# IO_Expander.net
KiCad netlist of a schematic drawn in EAGLE
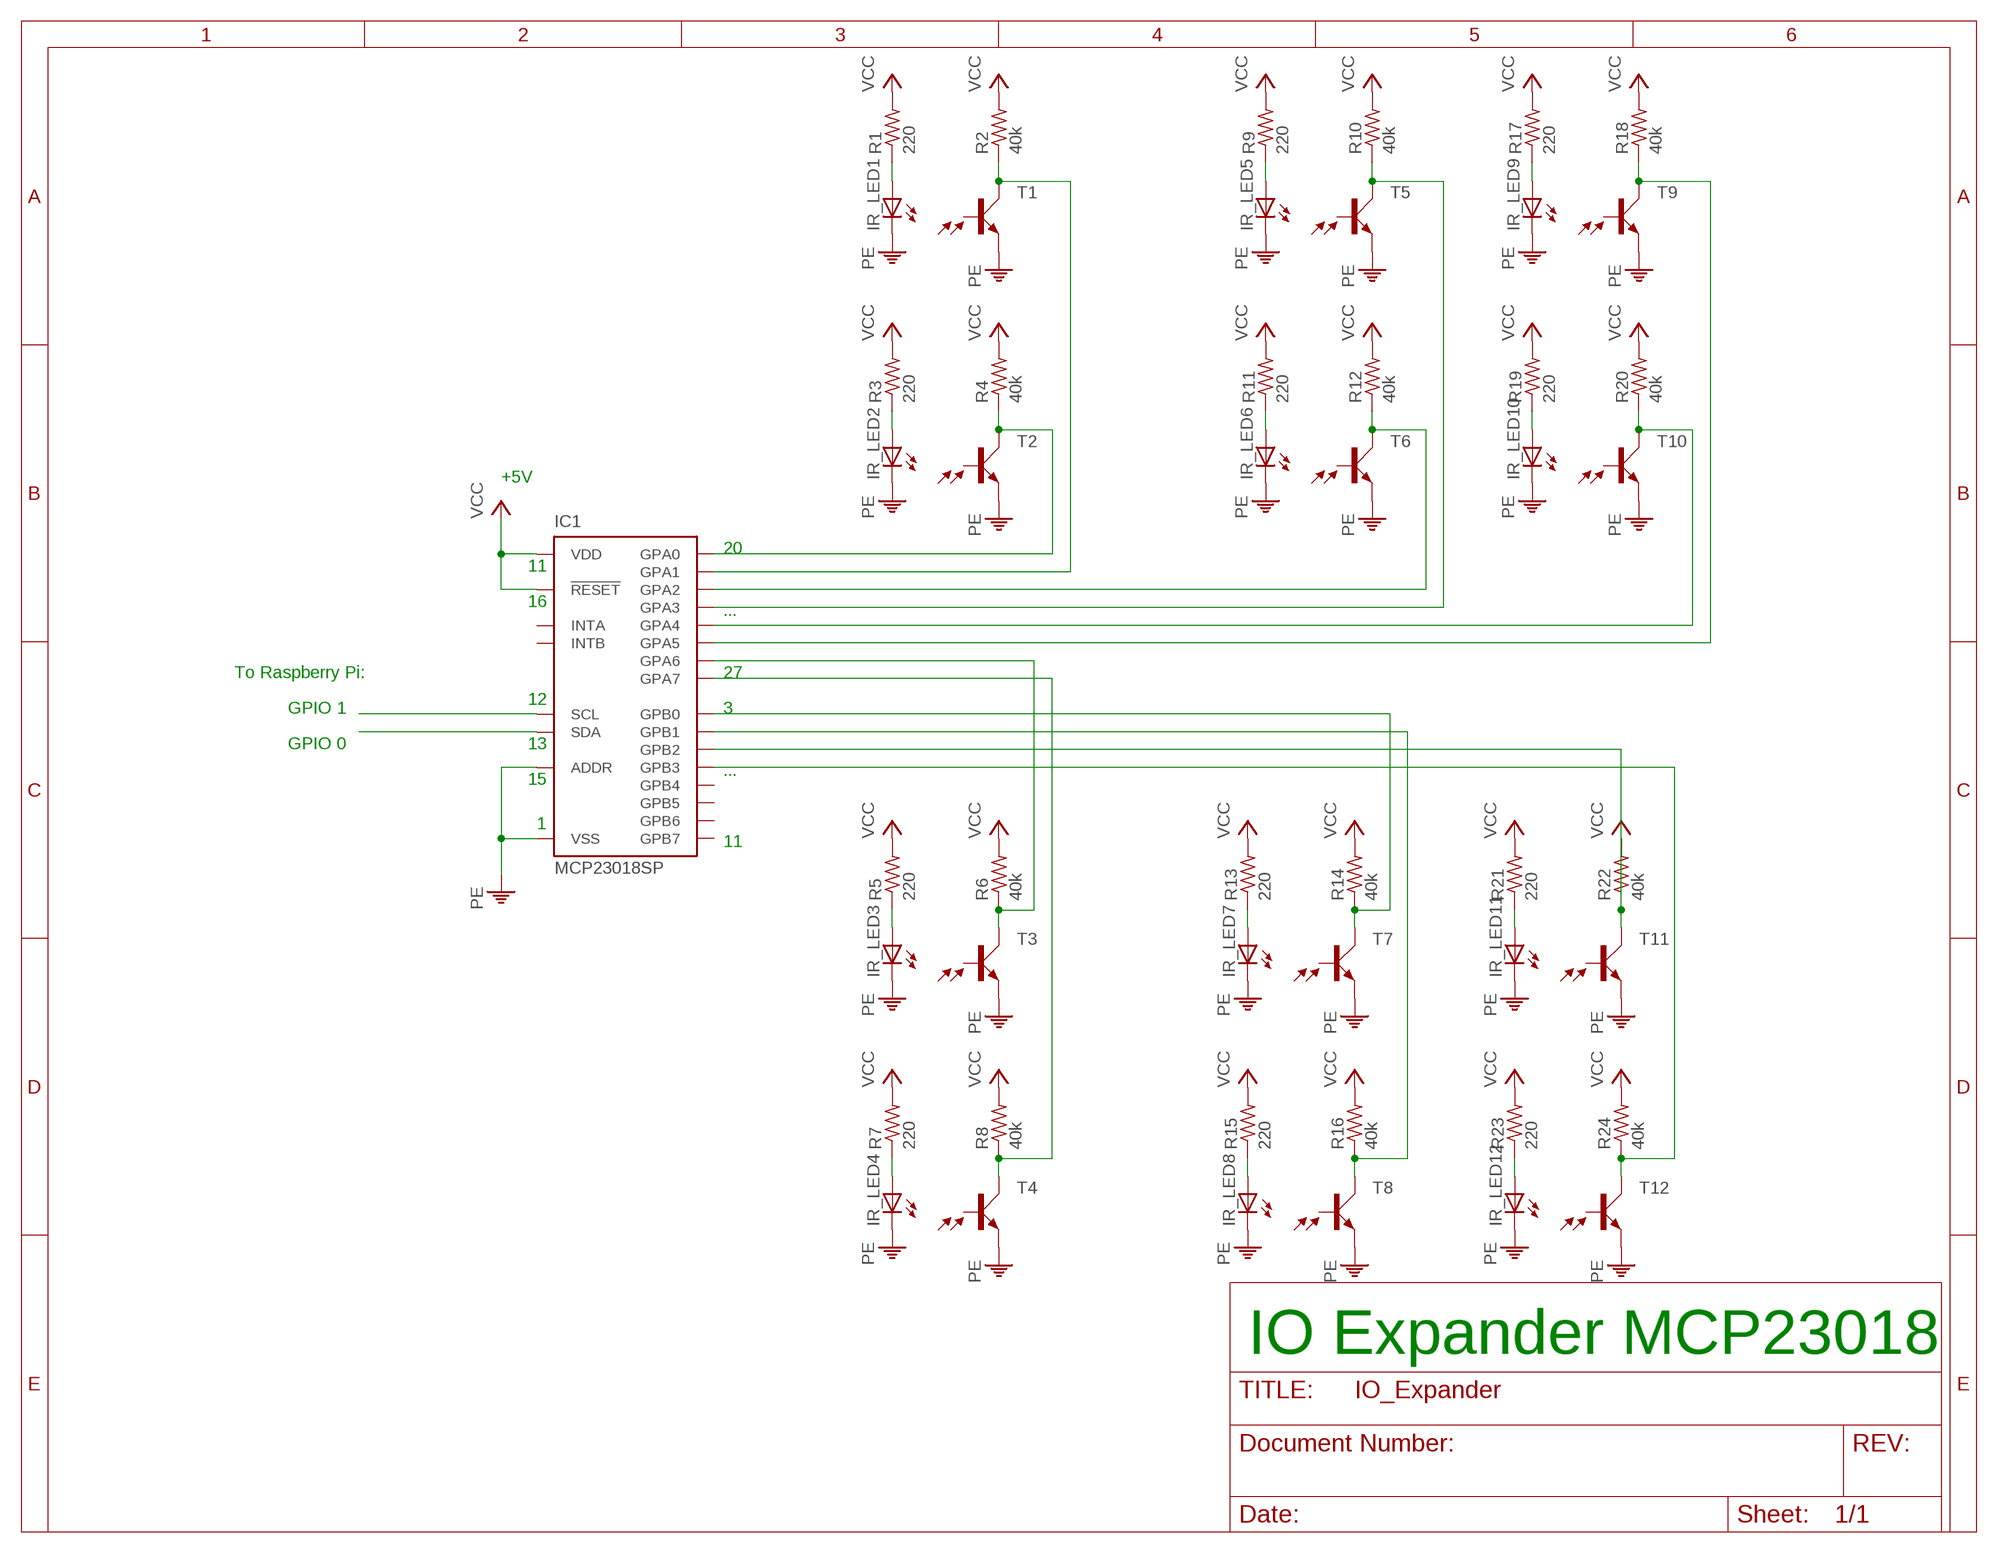
[diagram p0: schematic, sheet 1]

(export (version "E")
  (design (tool "Eeschema 10.0.6"))
  (components
    (comp (ref "IC1")
      (value "MCP23018SP")
      (footprint "eagle-import:DIL28-3")
      (libsource (lib "eagle-import") (part "MCP23018SP"))
    )
    (comp (ref "IR_LED1")
      (value "LED5MM")
      (footprint "eagle-import:LED5MM")
      (libsource (lib "eagle-import") (part "LED5MM"))
    )
    (comp (ref "IR_LED2")
      (value "LED5MM")
      (footprint "eagle-import:LED5MM")
      (libsource (lib "eagle-import") (part "LED5MM"))
    )
    (comp (ref "IR_LED3")
      (value "LED5MM")
      (footprint "eagle-import:LED5MM")
      (libsource (lib "eagle-import") (part "LED5MM"))
    )
    (comp (ref "IR_LED4")
      (value "LED5MM")
      (footprint "eagle-import:LED5MM")
      (libsource (lib "eagle-import") (part "LED5MM"))
    )
    (comp (ref "IR_LED5")
      (value "LED5MM")
      (footprint "eagle-import:LED5MM")
      (libsource (lib "eagle-import") (part "LED5MM"))
    )
    (comp (ref "IR_LED6")
      (value "LED5MM")
      (footprint "eagle-import:LED5MM")
      (libsource (lib "eagle-import") (part "LED5MM"))
    )
    (comp (ref "IR_LED7")
      (value "LED5MM")
      (footprint "eagle-import:LED5MM")
      (libsource (lib "eagle-import") (part "LED5MM"))
    )
    (comp (ref "IR_LED8")
      (value "LED5MM")
      (footprint "eagle-import:LED5MM")
      (libsource (lib "eagle-import") (part "LED5MM"))
    )
    (comp (ref "IR_LED9")
      (value "LED5MM")
      (footprint "eagle-import:LED5MM")
      (libsource (lib "eagle-import") (part "LED5MM"))
    )
    (comp (ref "IR_LED10")
      (value "LED5MM")
      (footprint "eagle-import:LED5MM")
      (libsource (lib "eagle-import") (part "LED5MM"))
    )
    (comp (ref "IR_LED11")
      (value "LED5MM")
      (footprint "eagle-import:LED5MM")
      (libsource (lib "eagle-import") (part "LED5MM"))
    )
    (comp (ref "IR_LED12")
      (value "LED5MM")
      (footprint "eagle-import:LED5MM")
      (libsource (lib "eagle-import") (part "LED5MM"))
    )
    (comp (ref "R1")
      (value "220")
      (footprint "eagle-import:0204_7")
      (libsource (lib "eagle-import") (part "R-US_0204/7"))
    )
    (comp (ref "R2")
      (value "40k")
      (footprint "eagle-import:0204_7")
      (libsource (lib "eagle-import") (part "R-US_0204/7"))
    )
    (comp (ref "R3")
      (value "220")
      (footprint "eagle-import:0204_7")
      (libsource (lib "eagle-import") (part "R-US_0204/7"))
    )
    (comp (ref "R4")
      (value "40k")
      (footprint "eagle-import:0204_7")
      (libsource (lib "eagle-import") (part "R-US_0204/7"))
    )
    (comp (ref "R5")
      (value "220")
      (footprint "eagle-import:0204_7")
      (libsource (lib "eagle-import") (part "R-US_0204/7"))
    )
    (comp (ref "R6")
      (value "40k")
      (footprint "eagle-import:0204_7")
      (libsource (lib "eagle-import") (part "R-US_0204/7"))
    )
    (comp (ref "R7")
      (value "220")
      (footprint "eagle-import:0204_7")
      (libsource (lib "eagle-import") (part "R-US_0204/7"))
    )
    (comp (ref "R8")
      (value "40k")
      (footprint "eagle-import:0204_7")
      (libsource (lib "eagle-import") (part "R-US_0204/7"))
    )
    (comp (ref "R9")
      (value "220")
      (footprint "eagle-import:0204_7")
      (libsource (lib "eagle-import") (part "R-US_0204/7"))
    )
    (comp (ref "R10")
      (value "40k")
      (footprint "eagle-import:0204_7")
      (libsource (lib "eagle-import") (part "R-US_0204/7"))
    )
    (comp (ref "R11")
      (value "220")
      (footprint "eagle-import:0204_7")
      (libsource (lib "eagle-import") (part "R-US_0204/7"))
    )
    (comp (ref "R12")
      (value "40k")
      (footprint "eagle-import:0204_7")
      (libsource (lib "eagle-import") (part "R-US_0204/7"))
    )
    (comp (ref "R13")
      (value "220")
      (footprint "eagle-import:0204_7")
      (libsource (lib "eagle-import") (part "R-US_0204/7"))
    )
    (comp (ref "R14")
      (value "40k")
      (footprint "eagle-import:0204_7")
      (libsource (lib "eagle-import") (part "R-US_0204/7"))
    )
    (comp (ref "R15")
      (value "220")
      (footprint "eagle-import:0204_7")
      (libsource (lib "eagle-import") (part "R-US_0204/7"))
    )
    (comp (ref "R16")
      (value "40k")
      (footprint "eagle-import:0204_7")
      (libsource (lib "eagle-import") (part "R-US_0204/7"))
    )
    (comp (ref "R17")
      (value "220")
      (footprint "eagle-import:0204_7")
      (libsource (lib "eagle-import") (part "R-US_0204/7"))
    )
    (comp (ref "R18")
      (value "40k")
      (footprint "eagle-import:0204_7")
      (libsource (lib "eagle-import") (part "R-US_0204/7"))
    )
    (comp (ref "R19")
      (value "220")
      (footprint "eagle-import:0204_7")
      (libsource (lib "eagle-import") (part "R-US_0204/7"))
    )
    (comp (ref "R20")
      (value "40k")
      (footprint "eagle-import:0204_7")
      (libsource (lib "eagle-import") (part "R-US_0204/7"))
    )
    (comp (ref "R21")
      (value "220")
      (footprint "eagle-import:0204_7")
      (libsource (lib "eagle-import") (part "R-US_0204/7"))
    )
    (comp (ref "R22")
      (value "40k")
      (footprint "eagle-import:0204_7")
      (libsource (lib "eagle-import") (part "R-US_0204/7"))
    )
    (comp (ref "R23")
      (value "220")
      (footprint "eagle-import:0204_7")
      (libsource (lib "eagle-import") (part "R-US_0204/7"))
    )
    (comp (ref "R24")
      (value "40k")
      (footprint "eagle-import:0204_7")
      (libsource (lib "eagle-import") (part "R-US_0204/7"))
    )
    (comp (ref "T1")
      (value "SFH303")
      (footprint "eagle-import:SFH303")
      (libsource (lib "eagle-import") (part "SFH303"))
    )
    (comp (ref "T2")
      (value "SFH303")
      (footprint "eagle-import:SFH303")
      (libsource (lib "eagle-import") (part "SFH303"))
    )
    (comp (ref "T3")
      (value "SFH303")
      (footprint "eagle-import:SFH303")
      (libsource (lib "eagle-import") (part "SFH303"))
    )
    (comp (ref "T4")
      (value "SFH303")
      (footprint "eagle-import:SFH303")
      (libsource (lib "eagle-import") (part "SFH303"))
    )
    (comp (ref "T5")
      (value "SFH303")
      (footprint "eagle-import:SFH303")
      (libsource (lib "eagle-import") (part "SFH303"))
    )
    (comp (ref "T6")
      (value "SFH303")
      (footprint "eagle-import:SFH303")
      (libsource (lib "eagle-import") (part "SFH303"))
    )
    (comp (ref "T7")
      (value "SFH303")
      (footprint "eagle-import:SFH303")
      (libsource (lib "eagle-import") (part "SFH303"))
    )
    (comp (ref "T8")
      (value "SFH303")
      (footprint "eagle-import:SFH303")
      (libsource (lib "eagle-import") (part "SFH303"))
    )
    (comp (ref "T9")
      (value "SFH303")
      (footprint "eagle-import:SFH303")
      (libsource (lib "eagle-import") (part "SFH303"))
    )
    (comp (ref "T10")
      (value "SFH303")
      (footprint "eagle-import:SFH303")
      (libsource (lib "eagle-import") (part "SFH303"))
    )
    (comp (ref "T11")
      (value "SFH303")
      (footprint "eagle-import:SFH303")
      (libsource (lib "eagle-import") (part "SFH303"))
    )
    (comp (ref "T12")
      (value "SFH303")
      (footprint "eagle-import:SFH303")
      (libsource (lib "eagle-import") (part "SFH303"))
    )
  )
  (nets
    (net (code "1") (name "Net-(IC1-GPA0)") (class "Default")
      (node (ref "IC1") (pin "20") (pinfunction "GPA0_20") (pintype "bidirectional"))
      (node (ref "R4") (pin "1") (pinfunction "1_1") (pintype "passive"))
      (node (ref "T2") (pin "2") (pinfunction "C_2") (pintype "passive"))
    )
    (net (code "2") (name "Net-(IC1-GPA1)") (class "Default")
      (node (ref "IC1") (pin "21") (pinfunction "GPA1_21") (pintype "bidirectional"))
      (node (ref "R2") (pin "1") (pinfunction "1_1") (pintype "passive"))
      (node (ref "T1") (pin "2") (pinfunction "C_2") (pintype "passive"))
    )
    (net (code "3") (name "Net-(IC1-GPA2)") (class "Default")
      (node (ref "IC1") (pin "22") (pinfunction "GPA2_22") (pintype "bidirectional"))
      (node (ref "R12") (pin "1") (pinfunction "1_1") (pintype "passive"))
      (node (ref "T6") (pin "2") (pinfunction "C_2") (pintype "passive"))
    )
    (net (code "4") (name "Net-(IC1-GPA3)") (class "Default")
      (node (ref "IC1") (pin "23") (pinfunction "GPA3_23") (pintype "bidirectional"))
      (node (ref "R10") (pin "1") (pinfunction "1_1") (pintype "passive"))
      (node (ref "T5") (pin "2") (pinfunction "C_2") (pintype "passive"))
    )
    (net (code "5") (name "Net-(IC1-GPA4)") (class "Default")
      (node (ref "IC1") (pin "24") (pinfunction "GPA4_24") (pintype "bidirectional"))
      (node (ref "R20") (pin "1") (pinfunction "1_1") (pintype "passive"))
      (node (ref "T10") (pin "2") (pinfunction "C_2") (pintype "passive"))
    )
    (net (code "6") (name "Net-(IC1-GPA5)") (class "Default")
      (node (ref "IC1") (pin "25") (pinfunction "GPA5_25") (pintype "bidirectional"))
      (node (ref "R18") (pin "1") (pinfunction "1_1") (pintype "passive"))
      (node (ref "T9") (pin "2") (pinfunction "C_2") (pintype "passive"))
    )
    (net (code "7") (name "Net-(IC1-GPA6)") (class "Default")
      (node (ref "IC1") (pin "26") (pinfunction "GPA6_26") (pintype "bidirectional"))
      (node (ref "R6") (pin "1") (pinfunction "1_1") (pintype "passive"))
      (node (ref "T3") (pin "2") (pinfunction "C_2") (pintype "passive"))
    )
    (net (code "8") (name "Net-(IC1-GPA7)") (class "Default")
      (node (ref "IC1") (pin "27") (pinfunction "GPA7_27") (pintype "bidirectional"))
      (node (ref "R8") (pin "1") (pinfunction "1_1") (pintype "passive"))
      (node (ref "T4") (pin "2") (pinfunction "C_2") (pintype "passive"))
    )
    (net (code "9") (name "Net-(IC1-GPB0)") (class "Default")
      (node (ref "IC1") (pin "3") (pinfunction "GPB0_3") (pintype "bidirectional"))
      (node (ref "R14") (pin "1") (pinfunction "1_1") (pintype "passive"))
      (node (ref "T7") (pin "2") (pinfunction "C_2") (pintype "passive"))
    )
    (net (code "10") (name "Net-(IC1-GPB1)") (class "Default")
      (node (ref "IC1") (pin "4") (pinfunction "GPB1_4") (pintype "bidirectional"))
      (node (ref "R16") (pin "1") (pinfunction "1_1") (pintype "passive"))
      (node (ref "T8") (pin "2") (pinfunction "C_2") (pintype "passive"))
    )
    (net (code "11") (name "Net-(IC1-GPB2)") (class "Default")
      (node (ref "IC1") (pin "5") (pinfunction "GPB2_5") (pintype "bidirectional"))
      (node (ref "R22") (pin "1") (pinfunction "1_1") (pintype "passive"))
      (node (ref "T11") (pin "2") (pinfunction "C_2") (pintype "passive"))
    )
    (net (code "12") (name "Net-(IC1-GPB3)") (class "Default")
      (node (ref "IC1") (pin "6") (pinfunction "GPB3_6") (pintype "bidirectional"))
      (node (ref "R24") (pin "1") (pinfunction "1_1") (pintype "passive"))
      (node (ref "T12") (pin "2") (pinfunction "C_2") (pintype "passive"))
    )
    (net (code "13") (name "Net-(IR_LED1-PadA)") (class "Default")
      (node (ref "IR_LED1") (pin "A") (pinfunction "A_A") (pintype "passive"))
      (node (ref "R1") (pin "1") (pinfunction "1_1") (pintype "passive"))
    )
    (net (code "14") (name "Net-(IR_LED2-PadA)") (class "Default")
      (node (ref "IR_LED2") (pin "A") (pinfunction "A_A") (pintype "passive"))
      (node (ref "R3") (pin "1") (pinfunction "1_1") (pintype "passive"))
    )
    (net (code "15") (name "Net-(IR_LED3-PadA)") (class "Default")
      (node (ref "IR_LED3") (pin "A") (pinfunction "A_A") (pintype "passive"))
      (node (ref "R5") (pin "1") (pinfunction "1_1") (pintype "passive"))
    )
    (net (code "16") (name "Net-(IR_LED4-PadA)") (class "Default")
      (node (ref "IR_LED4") (pin "A") (pinfunction "A_A") (pintype "passive"))
      (node (ref "R7") (pin "1") (pinfunction "1_1") (pintype "passive"))
    )
    (net (code "17") (name "Net-(IR_LED5-PadA)") (class "Default")
      (node (ref "IR_LED5") (pin "A") (pinfunction "A_A") (pintype "passive"))
      (node (ref "R9") (pin "1") (pinfunction "1_1") (pintype "passive"))
    )
    (net (code "18") (name "Net-(IR_LED6-PadA)") (class "Default")
      (node (ref "IR_LED6") (pin "A") (pinfunction "A_A") (pintype "passive"))
      (node (ref "R11") (pin "1") (pinfunction "1_1") (pintype "passive"))
    )
    (net (code "19") (name "Net-(IR_LED7-PadA)") (class "Default")
      (node (ref "IR_LED7") (pin "A") (pinfunction "A_A") (pintype "passive"))
      (node (ref "R13") (pin "1") (pinfunction "1_1") (pintype "passive"))
    )
    (net (code "20") (name "Net-(IR_LED8-PadA)") (class "Default")
      (node (ref "IR_LED8") (pin "A") (pinfunction "A_A") (pintype "passive"))
      (node (ref "R15") (pin "1") (pinfunction "1_1") (pintype "passive"))
    )
    (net (code "21") (name "Net-(IR_LED9-PadA)") (class "Default")
      (node (ref "IR_LED9") (pin "A") (pinfunction "A_A") (pintype "passive"))
      (node (ref "R17") (pin "1") (pinfunction "1_1") (pintype "passive"))
    )
    (net (code "22") (name "Net-(IR_LED10-PadA)") (class "Default")
      (node (ref "IR_LED10") (pin "A") (pinfunction "A_A") (pintype "passive"))
      (node (ref "R19") (pin "1") (pinfunction "1_1") (pintype "passive"))
    )
    (net (code "23") (name "Net-(IR_LED11-PadA)") (class "Default")
      (node (ref "IR_LED11") (pin "A") (pinfunction "A_A") (pintype "passive"))
      (node (ref "R21") (pin "1") (pinfunction "1_1") (pintype "passive"))
    )
    (net (code "24") (name "Net-(IR_LED12-PadA)") (class "Default")
      (node (ref "IR_LED12") (pin "A") (pinfunction "A_A") (pintype "passive"))
      (node (ref "R23") (pin "1") (pinfunction "1_1") (pintype "passive"))
    )
    (net (code "25") (name "PE") (class "Default")
      (node (ref "IC1") (pin "1") (pinfunction "VSS_1") (pintype "power_in"))
      (node (ref "IC1") (pin "15") (pinfunction "ADDR_15") (pintype "input"))
      (node (ref "IR_LED1") (pin "K") (pinfunction "C_K") (pintype "passive"))
      (node (ref "IR_LED10") (pin "K") (pinfunction "C_K") (pintype "passive"))
      (node (ref "IR_LED11") (pin "K") (pinfunction "C_K") (pintype "passive"))
      (node (ref "IR_LED12") (pin "K") (pinfunction "C_K") (pintype "passive"))
      (node (ref "IR_LED2") (pin "K") (pinfunction "C_K") (pintype "passive"))
      (node (ref "IR_LED3") (pin "K") (pinfunction "C_K") (pintype "passive"))
      (node (ref "IR_LED4") (pin "K") (pinfunction "C_K") (pintype "passive"))
      (node (ref "IR_LED5") (pin "K") (pinfunction "C_K") (pintype "passive"))
      (node (ref "IR_LED6") (pin "K") (pinfunction "C_K") (pintype "passive"))
      (node (ref "IR_LED7") (pin "K") (pinfunction "C_K") (pintype "passive"))
      (node (ref "IR_LED8") (pin "K") (pinfunction "C_K") (pintype "passive"))
      (node (ref "IR_LED9") (pin "K") (pinfunction "C_K") (pintype "passive"))
      (node (ref "T1") (pin "1") (pinfunction "E_1") (pintype "passive"))
      (node (ref "T10") (pin "1") (pinfunction "E_1") (pintype "passive"))
      (node (ref "T11") (pin "1") (pinfunction "E_1") (pintype "passive"))
      (node (ref "T12") (pin "1") (pinfunction "E_1") (pintype "passive"))
      (node (ref "T2") (pin "1") (pinfunction "E_1") (pintype "passive"))
      (node (ref "T3") (pin "1") (pinfunction "E_1") (pintype "passive"))
      (node (ref "T4") (pin "1") (pinfunction "E_1") (pintype "passive"))
      (node (ref "T5") (pin "1") (pinfunction "E_1") (pintype "passive"))
      (node (ref "T6") (pin "1") (pinfunction "E_1") (pintype "passive"))
      (node (ref "T7") (pin "1") (pinfunction "E_1") (pintype "passive"))
      (node (ref "T8") (pin "1") (pinfunction "E_1") (pintype "passive"))
      (node (ref "T9") (pin "1") (pinfunction "E_1") (pintype "passive"))
    )
    (net (code "26") (name "VCC") (class "Default")
      (node (ref "IC1") (pin "11") (pinfunction "VDD_11") (pintype "power_in"))
      (node (ref "IC1") (pin "16") (pinfunction "~{RESET}_16") (pintype "input"))
      (node (ref "R1") (pin "2") (pinfunction "2_2") (pintype "passive"))
      (node (ref "R10") (pin "2") (pinfunction "2_2") (pintype "passive"))
      (node (ref "R11") (pin "2") (pinfunction "2_2") (pintype "passive"))
      (node (ref "R12") (pin "2") (pinfunction "2_2") (pintype "passive"))
      (node (ref "R13") (pin "2") (pinfunction "2_2") (pintype "passive"))
      (node (ref "R14") (pin "2") (pinfunction "2_2") (pintype "passive"))
      (node (ref "R15") (pin "2") (pinfunction "2_2") (pintype "passive"))
      (node (ref "R16") (pin "2") (pinfunction "2_2") (pintype "passive"))
      (node (ref "R17") (pin "2") (pinfunction "2_2") (pintype "passive"))
      (node (ref "R18") (pin "2") (pinfunction "2_2") (pintype "passive"))
      (node (ref "R19") (pin "2") (pinfunction "2_2") (pintype "passive"))
      (node (ref "R2") (pin "2") (pinfunction "2_2") (pintype "passive"))
      (node (ref "R20") (pin "2") (pinfunction "2_2") (pintype "passive"))
      (node (ref "R21") (pin "2") (pinfunction "2_2") (pintype "passive"))
      (node (ref "R22") (pin "2") (pinfunction "2_2") (pintype "passive"))
      (node (ref "R23") (pin "2") (pinfunction "2_2") (pintype "passive"))
      (node (ref "R24") (pin "2") (pinfunction "2_2") (pintype "passive"))
      (node (ref "R3") (pin "2") (pinfunction "2_2") (pintype "passive"))
      (node (ref "R4") (pin "2") (pinfunction "2_2") (pintype "passive"))
      (node (ref "R5") (pin "2") (pinfunction "2_2") (pintype "passive"))
      (node (ref "R6") (pin "2") (pinfunction "2_2") (pintype "passive"))
      (node (ref "R7") (pin "2") (pinfunction "2_2") (pintype "passive"))
      (node (ref "R8") (pin "2") (pinfunction "2_2") (pintype "passive"))
      (node (ref "R9") (pin "2") (pinfunction "2_2") (pintype "passive"))
    )
    (net (code "27") (name "unconnected-(IC1-GPB4-Pad7)") (class "Default")
      (node (ref "IC1") (pin "7") (pinfunction "GPB4_7") (pintype "bidirectional"))
    )
    (net (code "28") (name "unconnected-(IC1-GPB5-Pad8)") (class "Default")
      (node (ref "IC1") (pin "8") (pinfunction "GPB5_8") (pintype "bidirectional"))
    )
    (net (code "29") (name "unconnected-(IC1-GPB6-Pad9)") (class "Default")
      (node (ref "IC1") (pin "9") (pinfunction "GPB6_9") (pintype "bidirectional"))
    )
    (net (code "30") (name "unconnected-(IC1-GPB7-Pad10)") (class "Default")
      (node (ref "IC1") (pin "10") (pinfunction "GPB7_10") (pintype "bidirectional"))
    )
    (net (code "31") (name "unconnected-(IC1-INTA-Pad19)") (class "Default")
      (node (ref "IC1") (pin "19") (pinfunction "INTA_19") (pintype "output"))
    )
    (net (code "32") (name "unconnected-(IC1-INTB-Pad18)") (class "Default")
      (node (ref "IC1") (pin "18") (pinfunction "INTB_18") (pintype "output"))
    )
    (net (code "33") (name "unconnected-(IC1-SCL-Pad12)") (class "Default")
      (node (ref "IC1") (pin "12") (pinfunction "SCL_12") (pintype "input"))
    )
    (net (code "34") (name "unconnected-(IC1-SDA-Pad13)") (class "Default")
      (node (ref "IC1") (pin "13") (pinfunction "SDA_13") (pintype "bidirectional"))
    )
    (net (code "35") (name "unconnected-(T1-B-Pad3)") (class "Default")
      (node (ref "T1") (pin "3") (pinfunction "B_3") (pintype "passive"))
    )
    (net (code "36") (name "unconnected-(T2-B-Pad3)") (class "Default")
      (node (ref "T2") (pin "3") (pinfunction "B_3") (pintype "passive"))
    )
    (net (code "37") (name "unconnected-(T3-B-Pad3)") (class "Default")
      (node (ref "T3") (pin "3") (pinfunction "B_3") (pintype "passive"))
    )
    (net (code "38") (name "unconnected-(T4-B-Pad3)") (class "Default")
      (node (ref "T4") (pin "3") (pinfunction "B_3") (pintype "passive"))
    )
    (net (code "39") (name "unconnected-(T5-B-Pad3)") (class "Default")
      (node (ref "T5") (pin "3") (pinfunction "B_3") (pintype "passive"))
    )
    (net (code "40") (name "unconnected-(T6-B-Pad3)") (class "Default")
      (node (ref "T6") (pin "3") (pinfunction "B_3") (pintype "passive"))
    )
    (net (code "41") (name "unconnected-(T7-B-Pad3)") (class "Default")
      (node (ref "T7") (pin "3") (pinfunction "B_3") (pintype "passive"))
    )
    (net (code "42") (name "unconnected-(T8-B-Pad3)") (class "Default")
      (node (ref "T8") (pin "3") (pinfunction "B_3") (pintype "passive"))
    )
    (net (code "43") (name "unconnected-(T9-B-Pad3)") (class "Default")
      (node (ref "T9") (pin "3") (pinfunction "B_3") (pintype "passive"))
    )
    (net (code "44") (name "unconnected-(T10-B-Pad3)") (class "Default")
      (node (ref "T10") (pin "3") (pinfunction "B_3") (pintype "passive"))
    )
    (net (code "45") (name "unconnected-(T11-B-Pad3)") (class "Default")
      (node (ref "T11") (pin "3") (pinfunction "B_3") (pintype "passive"))
    )
    (net (code "46") (name "unconnected-(T12-B-Pad3)") (class "Default")
      (node (ref "T12") (pin "3") (pinfunction "B_3") (pintype "passive"))
    )
  )
)
